# Current_measurement_circuit.net
KiCad netlist of a schematic drawn in Altium Designer
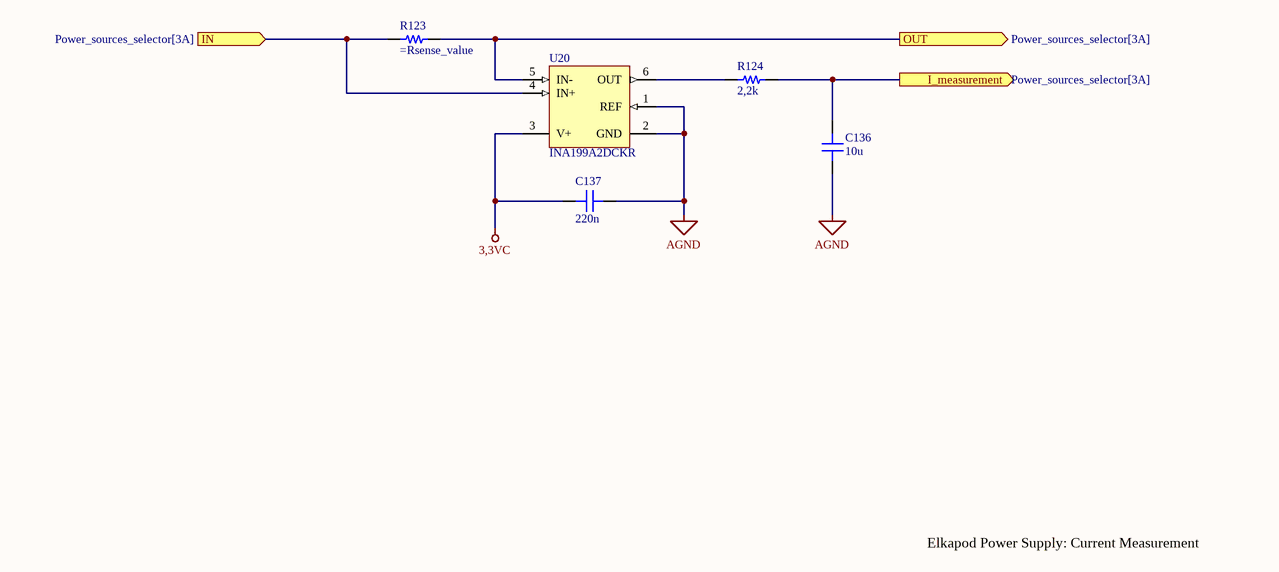
[diagram p0: Current_measurement_circuit.SchDoc]

(export (version "E")
  (design (tool "Eeschema 10.0.6"))
  (components
    (comp (ref "C136")
      (value "10u")
      (footprint "CAP 0603_1608")
      (description "CAP CER 10uF 35V X5R 0603")
      (fields (field (name "PART NUMBER") "C0603C272F3GAC7867") (field (name "MANUFACTURER") "KEMET"))
      (libsource (lib "Celestial Altium Library - altium_library") (part "Capacitor"))
    )
    (comp (ref "C137")
      (value "220n")
      (footprint "CAP 0603_1608")
      (description "CAP CER 220nF 25V X5R 0603")
      (fields (field (name "PART NUMBER") "C0603C272F3GAC7867") (field (name "MANUFACTURER") "KEMET"))
      (libsource (lib "Celestial Altium Library - altium_library") (part "Capacitor"))
    )
    (comp (ref "R123")
      (value "~")
      (footprint "STACKPOLE CSM2512")
      (description "RES 1% 3W 2512")
      (fields
        (field (name "PART NUMBER") "CSM2512FT20L0")
        (field (name "MANUFACTURER") "Stackpole Electronics Inc")
      )
      (libsource (lib "Celestial Altium Library - altium_library") (part "Resistor"))
    )
    (comp (ref "R124")
      (value "2,2k")
      (footprint "RES 0603_1608")
      (description "RES 2,2K OHM 1% 0,1W 0603")
      (fields
        (field (name "PART NUMBER") "RNCS0603BKE10K0")
        (field (name "MANUFACTURER") "Stackpole Electronics Inc")
      )
      (libsource (lib "Celestial Altium Library - altium_library") (part "Resistor"))
    )
    (comp (ref "U20")
      (value "INA199A2DCKR")
      (footprint "DCK0006A_N")
      (libsource (lib "Altium Content Vault") (part "TI-INA199A2DCK6"))
    )
  )
  (nets
    (net (code "1") (name "/IN") (class "Default")
      (node (ref "R123") (pin "2") (pinfunction "2_2") (pintype "passive"))
      (node (ref "U20") (pin "4") (pinfunction "IN+_4") (pintype "input"))
    )
    (net (code "2") (name "/I_measurement") (class "Default")
      (node (ref "C136") (pin "2") (pinfunction "2_2") (pintype "passive"))
      (node (ref "R124") (pin "2") (pinfunction "2_2") (pintype "passive"))
    )
    (net (code "3") (name "/OUT") (class "Default")
      (node (ref "R123") (pin "1") (pinfunction "1_1") (pintype "passive"))
      (node (ref "U20") (pin "5") (pinfunction "IN-_5") (pintype "input"))
    )
    (net (code "4") (name "3,3VC") (class "Default")
      (node (ref "C137") (pin "2") (pinfunction "2_2") (pintype "passive"))
      (node (ref "U20") (pin "3") (pinfunction "V+_3") (pintype "power_in"))
    )
    (net (code "5") (name "AGND") (class "Default")
      (node (ref "C136") (pin "1") (pinfunction "1_1") (pintype "passive"))
      (node (ref "C137") (pin "1") (pinfunction "1_1") (pintype "passive"))
      (node (ref "U20") (pin "1") (pinfunction "REF_1") (pintype "input"))
      (node (ref "U20") (pin "2") (pinfunction "GND_2") (pintype "power_in"))
    )
    (net (code "6") (name "Net-(U20-OUT)") (class "Default")
      (node (ref "R124") (pin "1") (pinfunction "1_1") (pintype "passive"))
      (node (ref "U20") (pin "6") (pinfunction "OUT_6") (pintype "output"))
    )
  )
)
